# OPA134.net
KiCad netlist of a schematic drawn in Altium Designer
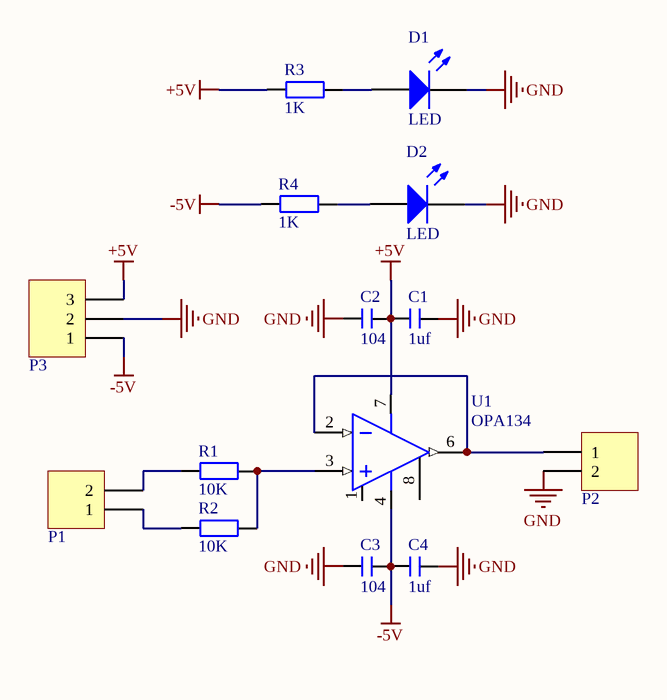
[diagram p0: OPA134同向加法器.SchDoc]

(export (version "E")
  (design (tool "Eeschema 10.0.6"))
  (components
    (comp (ref "C1")
      (value "1uf")
      (footprint "C 0805")
      (description "无极性贴片电容")
      (fields (field (name "版权归属") "源创客"))
      (libsource (lib "电阻-电容-电感") (part "C"))
    )
    (comp (ref "C2")
      (value "104")
      (footprint "C 0805")
      (description "无极性贴片电容")
      (fields (field (name "版权归属") "源创客"))
      (libsource (lib "电阻-电容-电感") (part "C"))
    )
    (comp (ref "C3")
      (value "104")
      (footprint "C 0805")
      (description "无极性贴片电容")
      (fields (field (name "版权归属") "源创客"))
      (libsource (lib "电阻-电容-电感") (part "C"))
    )
    (comp (ref "C4")
      (value "1uf")
      (footprint "C 0805")
      (description "无极性贴片电容")
      (fields (field (name "版权归属") "源创客"))
      (libsource (lib "电阻-电容-电感") (part "C"))
    )
    (comp (ref "D1")
      (value "LED")
      (footprint "LED_0805")
      (description "发光二极管")
      (fields (field (name "PUBLISHER") "Altium Limited"))
      (libsource (lib "LIB") (part "LED"))
    )
    (comp (ref "D2")
      (value "LED")
      (footprint "LED_0805")
      (description "发光二极管")
      (fields (field (name "PUBLISHER") "Altium Limited"))
      (libsource (lib "LIB") (part "LED"))
    )
    (comp (ref "P1")
      (value "Header 2")
      (footprint "HDR2X1_B2")
      (description "接插件")
      (fields (field (name "PUBLISHER") "Altium Limited"))
      (libsource (lib "") (part "Header 2_1"))
    )
    (comp (ref "P2")
      (value "Header 2")
      (footprint "HDR2X1_B2")
      (description "接插件")
      (fields (field (name "PUBLISHER") "Altium Limited"))
      (libsource (lib "LIB") (part "Header 2"))
    )
    (comp (ref "P3")
      (value "Header 3")
      (footprint "HDR3X1_B2")
      (description "接插件")
      (fields (field (name "PUBLISHER") "Altium Limited"))
      (libsource (lib "LIB") (part "Header 3"))
    )
    (comp (ref "R1")
      (value "10K")
      (footprint "R 0603")
      (description "贴片电阻")
      (fields (field (name "版权归属") "源创客"))
      (libsource (lib "电阻-电容-电感") (part "R"))
    )
    (comp (ref "R2")
      (value "10K")
      (footprint "R 0603")
      (description "贴片电阻")
      (fields (field (name "版权归属") "源创客"))
      (libsource (lib "电阻-电容-电感") (part "R"))
    )
    (comp (ref "R3")
      (value "1K")
      (footprint "R 0805")
      (description "贴片电阻")
      (fields (field (name "版权归属") "源创客"))
      (libsource (lib "电阻-电容-电感") (part "R"))
    )
    (comp (ref "R4")
      (value "1K")
      (footprint "R 0805")
      (description "贴片电阻")
      (fields (field (name "版权归属") "源创客"))
      (libsource (lib "电阻-电容-电感") (part "R"))
    )
    (comp (ref "U1")
      (value "OPA134")
      (footprint "SOIC8_N")
      (description "高性能音频运算放大器")
      (libsource (lib "LIB") (part "OPA134"))
    )
  )
  (nets
    (net (code "1") (name "+5V") (class "Default")
      (node (ref "C1") (pin "1") (pinfunction "1_1") (pintype "passive"))
      (node (ref "C2") (pin "2") (pinfunction "2_2") (pintype "passive"))
      (node (ref "P3") (pin "3") (pinfunction "3_3") (pintype "passive"))
      (node (ref "R3") (pin "1") (pinfunction "1_1") (pintype "passive"))
      (node (ref "U1") (pin "7") (pinfunction "V+_7") (pintype "power_in"))
    )
    (net (code "2") (name "-5V") (class "Default")
      (node (ref "C3") (pin "2") (pinfunction "2_2") (pintype "passive"))
      (node (ref "C4") (pin "1") (pinfunction "1_1") (pintype "passive"))
      (node (ref "P3") (pin "1") (pinfunction "1_1") (pintype "passive"))
      (node (ref "R4") (pin "1") (pinfunction "1_1") (pintype "passive"))
      (node (ref "U1") (pin "4") (pinfunction "V-_4") (pintype "power_in"))
    )
    (net (code "3") (name "GND") (class "Default")
      (node (ref "C1") (pin "2") (pinfunction "2_2") (pintype "passive"))
      (node (ref "C2") (pin "1") (pinfunction "1_1") (pintype "passive"))
      (node (ref "C3") (pin "1") (pinfunction "1_1") (pintype "passive"))
      (node (ref "C4") (pin "2") (pinfunction "2_2") (pintype "passive"))
      (node (ref "D1") (pin "2") (pinfunction "K_2") (pintype "passive"))
      (node (ref "D2") (pin "2") (pinfunction "K_2") (pintype "passive"))
      (node (ref "P2") (pin "2") (pinfunction "2_2") (pintype "passive"))
      (node (ref "P3") (pin "2") (pinfunction "2_2") (pintype "passive"))
    )
    (net (code "4") (name "Net-(D1-A)") (class "Default")
      (node (ref "D1") (pin "1") (pinfunction "A_1") (pintype "passive"))
      (node (ref "R3") (pin "2") (pinfunction "2_2") (pintype "passive"))
    )
    (net (code "5") (name "Net-(D2-A)") (class "Default")
      (node (ref "D2") (pin "1") (pinfunction "A_1") (pintype "passive"))
      (node (ref "R4") (pin "2") (pinfunction "2_2") (pintype "passive"))
    )
    (net (code "6") (name "Net-(P1-Pad1)") (class "Default")
      (node (ref "P1") (pin "1") (pinfunction "1_1") (pintype "passive"))
      (node (ref "R2") (pin "1") (pinfunction "1_1") (pintype "passive"))
    )
    (net (code "7") (name "Net-(P1-Pad2)") (class "Default")
      (node (ref "P1") (pin "2") (pinfunction "2_2") (pintype "passive"))
      (node (ref "R1") (pin "1") (pinfunction "1_1") (pintype "passive"))
    )
    (net (code "8") (name "Net-(U1-IN+)") (class "Default")
      (node (ref "R1") (pin "2") (pinfunction "2_2") (pintype "passive"))
      (node (ref "R2") (pin "2") (pinfunction "2_2") (pintype "passive"))
      (node (ref "U1") (pin "3") (pinfunction "IN+_3") (pintype "input"))
    )
    (net (code "9") (name "Net-(U1-IN-)") (class "Default")
      (node (ref "P2") (pin "1") (pinfunction "1_1") (pintype "passive"))
      (node (ref "U1") (pin "2") (pinfunction "IN-_2") (pintype "input"))
      (node (ref "U1") (pin "6") (pinfunction "OUT_6") (pintype "output"))
    )
    (net (code "10") (name "unconnected-(U1-OFFSET_N1-Pad1)") (class "Default")
      (node (ref "U1") (pin "1") (pinfunction "OFFSET_N1_1") (pintype "passive"))
    )
    (net (code "11") (name "unconnected-(U1-OFFSET_N2-Pad8)") (class "Default")
      (node (ref "U1") (pin "8") (pinfunction "OFFSET_N2_8") (pintype "passive"))
    )
  )
)
